# rpi2dmd-pi1B-v2.net
KiCad netlist of a schematic drawn in EAGLE
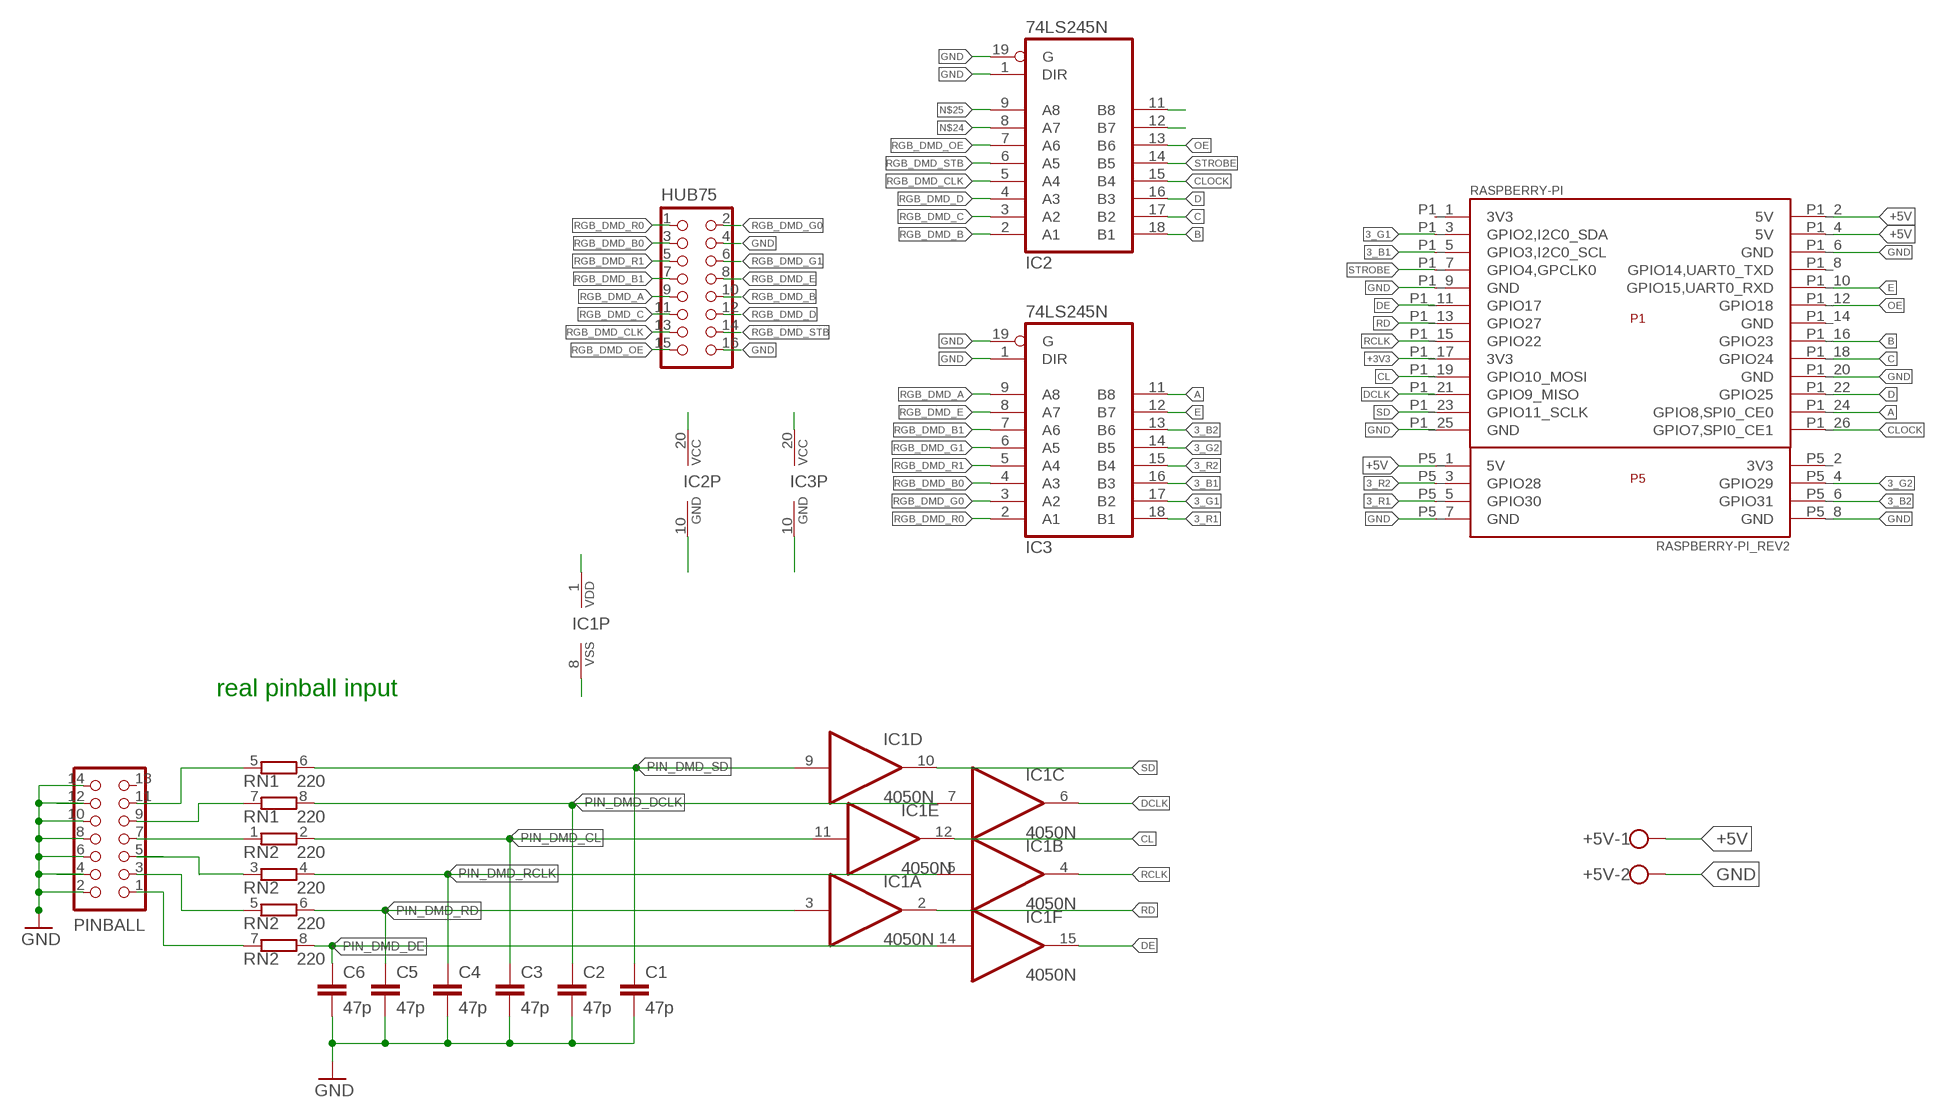
[diagram p0: schematic, sheet 1]

(export (version "E")
  (design (tool "Eeschema 10.0.6"))
  (components
    (comp (ref "+5V")
      (value "W237-102")
      (footprint "eagle-import:W237-102")
      (fields (field (name "MPN") "237-102"))
      (libsource (lib "eagle-import") (part "W237-102"))
    )
    (comp (ref "C1")
      (value "47p")
      (footprint "eagle-import:C025-024X044")
      (libsource (lib "eagle-import") (part "C-EU025-024X044"))
    )
    (comp (ref "C2")
      (value "47p")
      (footprint "eagle-import:C025-024X044")
      (libsource (lib "eagle-import") (part "C-EU025-024X044"))
    )
    (comp (ref "C3")
      (value "47p")
      (footprint "eagle-import:C025-024X044")
      (libsource (lib "eagle-import") (part "C-EU025-024X044"))
    )
    (comp (ref "C4")
      (value "47p")
      (footprint "eagle-import:C025-024X044")
      (libsource (lib "eagle-import") (part "C-EU025-024X044"))
    )
    (comp (ref "C5")
      (value "47p")
      (footprint "eagle-import:C025-024X044")
      (libsource (lib "eagle-import") (part "C-EU025-024X044"))
    )
    (comp (ref "C6")
      (value "47p")
      (footprint "eagle-import:C025-024X044")
      (libsource (lib "eagle-import") (part "C-EU025-024X044"))
    )
    (comp (ref "HUB75")
      (value "CON_HEADER_2X08B")
      (footprint "eagle-import:PINSHRD_PTH_2X08")
      (libsource (lib "eagle-import") (part "CON_HEADER_2X08B"))
    )
    (comp (ref "IC1")
      (value "4050N")
      (footprint "eagle-import:DIL16")
      (libsource (lib "eagle-import") (part "4050N"))
    )
    (comp (ref "IC2")
      (value "74LS245N")
      (footprint "eagle-import:DIL20")
      (libsource (lib "eagle-import") (part "74245NLS"))
    )
    (comp (ref "IC3")
      (value "74LS245N")
      (footprint "eagle-import:DIL20")
      (libsource (lib "eagle-import") (part "74245NLS"))
    )
    (comp (ref "PINBALL")
      (value "CON_HEADER_2X07-PTH-SHROUDED")
      (footprint "eagle-import:PINSHRD_PTH_2X07")
      (libsource (lib "eagle-import") (part "CON_HEADER_2X07-PTH-SHROUDED"))
    )
    (comp (ref "RASPBERRY-PI")
      (value "RASPBERRY-PI_REV2")
      (footprint "eagle-import:RASPBERRY-PI_REV2")
      (libsource (lib "eagle-import") (part "RASPBERRY-PI_REV2"))
    )
    (comp (ref "RN1")
      (value "220")
      (footprint "eagle-import:SIL8")
      (libsource (lib "eagle-import") (part "E4RP"))
    )
    (comp (ref "RN2")
      (value "220")
      (footprint "eagle-import:SIL8")
      (libsource (lib "eagle-import") (part "E4RP"))
    )
  )
  (nets
    (net (code "1") (name "+3V3") (class "Default")
      (node (ref "IC1") (pin "1") (pinfunction "VDD_1") (pintype "power_in"))
      (node (ref "RASPBERRY-PI") (pin "P1_17") (pinfunction "3V3_P1_17") (pintype "bidirectional"))
    )
    (net (code "2") (name "+5V") (class "Default")
      (node (ref "+5V") (pin "1") (pinfunction "KL_1") (pintype "passive"))
      (node (ref "IC2") (pin "20") (pinfunction "VCC_20") (pintype "power_in"))
      (node (ref "IC3") (pin "20") (pinfunction "VCC_20") (pintype "power_in"))
      (node (ref "RASPBERRY-PI") (pin "P1_2") (pinfunction "5V_P1_2") (pintype "bidirectional"))
      (node (ref "RASPBERRY-PI") (pin "P1_4") (pinfunction "5V_P1_4") (pintype "bidirectional"))
      (node (ref "RASPBERRY-PI") (pin "P5_1") (pinfunction "5V_P5_1") (pintype "bidirectional"))
    )
    (net (code "3") (name "3_B1") (class "Default")
      (node (ref "IC3") (pin "16") (pinfunction "B3_16") (pintype "bidirectional"))
      (node (ref "RASPBERRY-PI") (pin "P1_5") (pinfunction "GPIO3,I2C0_SCL_P1_5") (pintype "bidirectional"))
    )
    (net (code "4") (name "3_B2") (class "Default")
      (node (ref "IC3") (pin "13") (pinfunction "B6_13") (pintype "bidirectional"))
      (node (ref "RASPBERRY-PI") (pin "P5_6") (pinfunction "GPIO31_P5_6") (pintype "bidirectional"))
    )
    (net (code "5") (name "3_G1") (class "Default")
      (node (ref "IC3") (pin "17") (pinfunction "B2_17") (pintype "bidirectional"))
      (node (ref "RASPBERRY-PI") (pin "P1_3") (pinfunction "GPIO2,I2C0_SDA_P1_3") (pintype "bidirectional"))
    )
    (net (code "6") (name "3_G2") (class "Default")
      (node (ref "IC3") (pin "14") (pinfunction "B5_14") (pintype "bidirectional"))
      (node (ref "RASPBERRY-PI") (pin "P5_4") (pinfunction "GPIO29_P5_4") (pintype "bidirectional"))
    )
    (net (code "7") (name "3_R1") (class "Default")
      (node (ref "IC3") (pin "18") (pinfunction "B1_18") (pintype "bidirectional"))
      (node (ref "RASPBERRY-PI") (pin "P5_5") (pinfunction "GPIO30_P5_5") (pintype "bidirectional"))
    )
    (net (code "8") (name "3_R2") (class "Default")
      (node (ref "IC3") (pin "15") (pinfunction "B4_15") (pintype "bidirectional"))
      (node (ref "RASPBERRY-PI") (pin "P5_3") (pinfunction "GPIO28_P5_3") (pintype "bidirectional"))
    )
    (net (code "9") (name "A") (class "Default")
      (node (ref "IC3") (pin "11") (pinfunction "B8_11") (pintype "bidirectional"))
      (node (ref "RASPBERRY-PI") (pin "P1_24") (pinfunction "GPIO8,SPI0_CE0_P1_24") (pintype "bidirectional"))
    )
    (net (code "10") (name "B") (class "Default")
      (node (ref "IC2") (pin "18") (pinfunction "B1_18") (pintype "bidirectional"))
      (node (ref "RASPBERRY-PI") (pin "P1_16") (pinfunction "GPIO23_P1_16") (pintype "bidirectional"))
    )
    (net (code "11") (name "C") (class "Default")
      (node (ref "IC2") (pin "17") (pinfunction "B2_17") (pintype "bidirectional"))
      (node (ref "RASPBERRY-PI") (pin "P1_18") (pinfunction "GPIO24_P1_18") (pintype "bidirectional"))
    )
    (net (code "12") (name "CL") (class "Default")
      (node (ref "IC1") (pin "12") (pinfunction "O_12") (pintype "output"))
      (node (ref "RASPBERRY-PI") (pin "P1_19") (pinfunction "GPIO10_MOSI_P1_19") (pintype "bidirectional"))
    )
    (net (code "13") (name "CLOCK") (class "Default")
      (node (ref "IC2") (pin "15") (pinfunction "B4_15") (pintype "bidirectional"))
      (node (ref "RASPBERRY-PI") (pin "P1_26") (pinfunction "GPIO7,SPI0_CE1_P1_26") (pintype "bidirectional"))
    )
    (net (code "14") (name "D") (class "Default")
      (node (ref "IC2") (pin "16") (pinfunction "B3_16") (pintype "bidirectional"))
      (node (ref "RASPBERRY-PI") (pin "P1_22") (pinfunction "GPIO25_P1_22") (pintype "bidirectional"))
    )
    (net (code "15") (name "DCLK") (class "Default")
      (node (ref "IC1") (pin "6") (pinfunction "O_6") (pintype "output"))
      (node (ref "RASPBERRY-PI") (pin "P1_21") (pinfunction "GPIO9_MISO_P1_21") (pintype "bidirectional"))
    )
    (net (code "16") (name "DE") (class "Default")
      (node (ref "IC1") (pin "15") (pinfunction "O_15") (pintype "output"))
      (node (ref "RASPBERRY-PI") (pin "P1_11") (pinfunction "GPIO17_P1_11") (pintype "bidirectional"))
    )
    (net (code "17") (name "E") (class "Default")
      (node (ref "IC3") (pin "12") (pinfunction "B7_12") (pintype "bidirectional"))
      (node (ref "RASPBERRY-PI") (pin "P1_10") (pinfunction "GPIO15,UART0_RXD_P1_10") (pintype "bidirectional"))
    )
    (net (code "18") (name "GND") (class "Default")
      (node (ref "+5V") (pin "2") (pinfunction "KL_2") (pintype "passive"))
      (node (ref "C1") (pin "2") (pinfunction "2_2") (pintype "passive"))
      (node (ref "C2") (pin "2") (pinfunction "2_2") (pintype "passive"))
      (node (ref "C3") (pin "2") (pinfunction "2_2") (pintype "passive"))
      (node (ref "C4") (pin "2") (pinfunction "2_2") (pintype "passive"))
      (node (ref "C5") (pin "2") (pinfunction "2_2") (pintype "passive"))
      (node (ref "C6") (pin "2") (pinfunction "2_2") (pintype "passive"))
      (node (ref "HUB75") (pin "16") (pinfunction "16_16") (pintype "passive"))
      (node (ref "HUB75") (pin "4") (pinfunction "4_4") (pintype "passive"))
      (node (ref "IC1") (pin "8") (pinfunction "VSS_8") (pintype "power_in"))
      (node (ref "IC2") (pin "1") (pinfunction "DIR_1") (pintype "input"))
      (node (ref "IC2") (pin "10") (pinfunction "GND_10") (pintype "power_in"))
      (node (ref "IC2") (pin "19") (pinfunction "G_19") (pintype "input"))
      (node (ref "IC3") (pin "1") (pinfunction "DIR_1") (pintype "input"))
      (node (ref "IC3") (pin "10") (pinfunction "GND_10") (pintype "power_in"))
      (node (ref "IC3") (pin "19") (pinfunction "G_19") (pintype "input"))
      (node (ref "PINBALL") (pin "10") (pinfunction "10_10") (pintype "passive"))
      (node (ref "PINBALL") (pin "12") (pinfunction "12_12") (pintype "passive"))
      (node (ref "PINBALL") (pin "14") (pinfunction "14_14") (pintype "passive"))
      (node (ref "PINBALL") (pin "2") (pinfunction "2_2") (pintype "passive"))
      (node (ref "PINBALL") (pin "4") (pinfunction "4_4") (pintype "passive"))
      (node (ref "PINBALL") (pin "6") (pinfunction "6_6") (pintype "passive"))
      (node (ref "PINBALL") (pin "8") (pinfunction "8_8") (pintype "passive"))
      (node (ref "RASPBERRY-PI") (pin "P1_20") (pinfunction "GND_P1_20") (pintype "bidirectional"))
      (node (ref "RASPBERRY-PI") (pin "P1_25") (pinfunction "GND_P1_25") (pintype "bidirectional"))
      (node (ref "RASPBERRY-PI") (pin "P1_6") (pinfunction "GND_P1_6") (pintype "bidirectional"))
      (node (ref "RASPBERRY-PI") (pin "P1_9") (pinfunction "GND_P1_9") (pintype "bidirectional"))
      (node (ref "RASPBERRY-PI") (pin "P5_7") (pinfunction "GND_P5_7") (pintype "bidirectional"))
      (node (ref "RASPBERRY-PI") (pin "P5_8") (pinfunction "GND_P5_8") (pintype "bidirectional"))
    )
    (net (code "19") (name "N$24") (class "Default")
      (node (ref "IC2") (pin "8") (pinfunction "A7_8") (pintype "bidirectional"))
    )
    (net (code "20") (name "N$25") (class "Default")
      (node (ref "IC2") (pin "9") (pinfunction "A8_9") (pintype "bidirectional"))
    )
    (net (code "21") (name "Net-(PINBALL-Pad7)") (class "Default")
      (node (ref "PINBALL") (pin "7") (pinfunction "7_7") (pintype "passive"))
      (node (ref "RN2") (pin "1") (pinfunction "1_1") (pintype "passive"))
    )
    (net (code "22") (name "Net-(RN1C-1)") (class "Default")
      (node (ref "PINBALL") (pin "11") (pinfunction "11_11") (pintype "passive"))
      (node (ref "RN1") (pin "5") (pinfunction "1_5") (pintype "passive"))
    )
    (net (code "23") (name "Net-(RN1D-1)") (class "Default")
      (node (ref "PINBALL") (pin "9") (pinfunction "9_9") (pintype "passive"))
      (node (ref "RN1") (pin "7") (pinfunction "1_7") (pintype "passive"))
    )
    (net (code "24") (name "Net-(RN2B-1)") (class "Default")
      (node (ref "PINBALL") (pin "5") (pinfunction "5_5") (pintype "passive"))
      (node (ref "RN2") (pin "3") (pinfunction "1_3") (pintype "passive"))
    )
    (net (code "25") (name "Net-(RN2C-1)") (class "Default")
      (node (ref "PINBALL") (pin "3") (pinfunction "3_3") (pintype "passive"))
      (node (ref "RN2") (pin "5") (pinfunction "1_5") (pintype "passive"))
    )
    (net (code "26") (name "Net-(RN2D-1)") (class "Default")
      (node (ref "PINBALL") (pin "1") (pinfunction "1_1") (pintype "passive"))
      (node (ref "RN2") (pin "7") (pinfunction "1_7") (pintype "passive"))
    )
    (net (code "27") (name "OE") (class "Default")
      (node (ref "IC2") (pin "13") (pinfunction "B6_13") (pintype "bidirectional"))
      (node (ref "RASPBERRY-PI") (pin "P1_12") (pinfunction "GPIO18_P1_12") (pintype "bidirectional"))
    )
    (net (code "28") (name "PIN_DMD_CL") (class "Default")
      (node (ref "C3") (pin "1") (pinfunction "1_1") (pintype "passive"))
      (node (ref "IC1") (pin "11") (pinfunction "I_11") (pintype "input"))
      (node (ref "RN2") (pin "2") (pinfunction "2_2") (pintype "passive"))
    )
    (net (code "29") (name "PIN_DMD_DCLK") (class "Default")
      (node (ref "C2") (pin "1") (pinfunction "1_1") (pintype "passive"))
      (node (ref "IC1") (pin "7") (pinfunction "I_7") (pintype "input"))
      (node (ref "RN1") (pin "8") (pinfunction "2_8") (pintype "passive"))
    )
    (net (code "30") (name "PIN_DMD_DE") (class "Default")
      (node (ref "C6") (pin "1") (pinfunction "1_1") (pintype "passive"))
      (node (ref "IC1") (pin "14") (pinfunction "I_14") (pintype "input"))
      (node (ref "RN2") (pin "8") (pinfunction "2_8") (pintype "passive"))
    )
    (net (code "31") (name "PIN_DMD_RCLK") (class "Default")
      (node (ref "C4") (pin "1") (pinfunction "1_1") (pintype "passive"))
      (node (ref "IC1") (pin "5") (pinfunction "I_5") (pintype "input"))
      (node (ref "RN2") (pin "4") (pinfunction "2_4") (pintype "passive"))
    )
    (net (code "32") (name "PIN_DMD_RD") (class "Default")
      (node (ref "C5") (pin "1") (pinfunction "1_1") (pintype "passive"))
      (node (ref "IC1") (pin "3") (pinfunction "I_3") (pintype "input"))
      (node (ref "RN2") (pin "6") (pinfunction "2_6") (pintype "passive"))
    )
    (net (code "33") (name "PIN_DMD_SD") (class "Default")
      (node (ref "C1") (pin "1") (pinfunction "1_1") (pintype "passive"))
      (node (ref "IC1") (pin "9") (pinfunction "I_9") (pintype "input"))
      (node (ref "RN1") (pin "6") (pinfunction "2_6") (pintype "passive"))
    )
    (net (code "34") (name "RCLK") (class "Default")
      (node (ref "IC1") (pin "4") (pinfunction "O_4") (pintype "output"))
      (node (ref "RASPBERRY-PI") (pin "P1_15") (pinfunction "GPIO22_P1_15") (pintype "bidirectional"))
    )
    (net (code "35") (name "RD") (class "Default")
      (node (ref "IC1") (pin "2") (pinfunction "O_2") (pintype "output"))
      (node (ref "RASPBERRY-PI") (pin "P1_13") (pinfunction "GPIO27_P1_13") (pintype "bidirectional"))
    )
    (net (code "36") (name "RGB_DMD_A") (class "Default")
      (node (ref "HUB75") (pin "9") (pinfunction "9_9") (pintype "passive"))
      (node (ref "IC3") (pin "9") (pinfunction "A8_9") (pintype "bidirectional"))
    )
    (net (code "37") (name "RGB_DMD_B") (class "Default")
      (node (ref "HUB75") (pin "10") (pinfunction "10_10") (pintype "passive"))
      (node (ref "IC2") (pin "2") (pinfunction "A1_2") (pintype "bidirectional"))
    )
    (net (code "38") (name "RGB_DMD_B0") (class "Default")
      (node (ref "HUB75") (pin "3") (pinfunction "3_3") (pintype "passive"))
      (node (ref "IC3") (pin "4") (pinfunction "A3_4") (pintype "bidirectional"))
    )
    (net (code "39") (name "RGB_DMD_B1") (class "Default")
      (node (ref "HUB75") (pin "7") (pinfunction "7_7") (pintype "passive"))
      (node (ref "IC3") (pin "7") (pinfunction "A6_7") (pintype "bidirectional"))
    )
    (net (code "40") (name "RGB_DMD_C") (class "Default")
      (node (ref "HUB75") (pin "11") (pinfunction "11_11") (pintype "passive"))
      (node (ref "IC2") (pin "3") (pinfunction "A2_3") (pintype "bidirectional"))
    )
    (net (code "41") (name "RGB_DMD_CLK") (class "Default")
      (node (ref "HUB75") (pin "13") (pinfunction "13_13") (pintype "passive"))
      (node (ref "IC2") (pin "5") (pinfunction "A4_5") (pintype "bidirectional"))
    )
    (net (code "42") (name "RGB_DMD_D") (class "Default")
      (node (ref "HUB75") (pin "12") (pinfunction "12_12") (pintype "passive"))
      (node (ref "IC2") (pin "4") (pinfunction "A3_4") (pintype "bidirectional"))
    )
    (net (code "43") (name "RGB_DMD_E") (class "Default")
      (node (ref "HUB75") (pin "8") (pinfunction "8_8") (pintype "passive"))
      (node (ref "IC3") (pin "8") (pinfunction "A7_8") (pintype "bidirectional"))
    )
    (net (code "44") (name "RGB_DMD_G0") (class "Default")
      (node (ref "HUB75") (pin "2") (pinfunction "2_2") (pintype "passive"))
      (node (ref "IC3") (pin "3") (pinfunction "A2_3") (pintype "bidirectional"))
    )
    (net (code "45") (name "RGB_DMD_G1") (class "Default")
      (node (ref "HUB75") (pin "6") (pinfunction "6_6") (pintype "passive"))
      (node (ref "IC3") (pin "6") (pinfunction "A5_6") (pintype "bidirectional"))
    )
    (net (code "46") (name "RGB_DMD_OE") (class "Default")
      (node (ref "HUB75") (pin "15") (pinfunction "15_15") (pintype "passive"))
      (node (ref "IC2") (pin "7") (pinfunction "A6_7") (pintype "bidirectional"))
    )
    (net (code "47") (name "RGB_DMD_R0") (class "Default")
      (node (ref "HUB75") (pin "1") (pinfunction "1_1") (pintype "passive"))
      (node (ref "IC3") (pin "2") (pinfunction "A1_2") (pintype "bidirectional"))
    )
    (net (code "48") (name "RGB_DMD_R1") (class "Default")
      (node (ref "HUB75") (pin "5") (pinfunction "5_5") (pintype "passive"))
      (node (ref "IC3") (pin "5") (pinfunction "A4_5") (pintype "bidirectional"))
    )
    (net (code "49") (name "RGB_DMD_STB") (class "Default")
      (node (ref "HUB75") (pin "14") (pinfunction "14_14") (pintype "passive"))
      (node (ref "IC2") (pin "6") (pinfunction "A5_6") (pintype "bidirectional"))
    )
    (net (code "50") (name "SD") (class "Default")
      (node (ref "IC1") (pin "10") (pinfunction "O_10") (pintype "output"))
      (node (ref "RASPBERRY-PI") (pin "P1_23") (pinfunction "GPIO11_SCLK_P1_23") (pintype "bidirectional"))
    )
    (net (code "51") (name "STROBE") (class "Default")
      (node (ref "IC2") (pin "14") (pinfunction "B5_14") (pintype "bidirectional"))
      (node (ref "RASPBERRY-PI") (pin "P1_7") (pinfunction "GPIO4,GPCLK0_P1_7") (pintype "bidirectional"))
    )
    (net (code "52") (name "unconnected-(IC2A-B7-Pad12)") (class "Default")
      (node (ref "IC2") (pin "12") (pinfunction "B7_12") (pintype "bidirectional"))
    )
    (net (code "53") (name "unconnected-(IC2A-B8-Pad11)") (class "Default")
      (node (ref "IC2") (pin "11") (pinfunction "B8_11") (pintype "bidirectional"))
    )
    (net (code "54") (name "unconnected-(PINBALL-Pad13)") (class "Default")
      (node (ref "PINBALL") (pin "13") (pinfunction "13_13") (pintype "passive"))
    )
    (net (code "55") (name "unconnected-(RASPBERRY-PI-3V3-PadP1_1)") (class "Default")
      (node (ref "RASPBERRY-PI") (pin "P1_1") (pinfunction "3V3_P1_1") (pintype "bidirectional"))
    )
    (net (code "56") (name "unconnected-(RASPBERRY-PI-3V3-PadP5_2)") (class "Default")
      (node (ref "RASPBERRY-PI") (pin "P5_2") (pinfunction "3V3_P5_2") (pintype "bidirectional"))
    )
    (net (code "57") (name "unconnected-(RASPBERRY-PI-GND-PadP1_14)") (class "Default")
      (node (ref "RASPBERRY-PI") (pin "P1_14") (pinfunction "GND_P1_14") (pintype "bidirectional"))
    )
    (net (code "58") (name "unconnected-(RASPBERRY-PI-GPIO14,UART0_TXD-PadP1_8)") (class "Default")
      (node (ref "RASPBERRY-PI") (pin "P1_8") (pinfunction "GPIO14,UART0_TXD_P1_8") (pintype "bidirectional"))
    )
  )
)
